# Electronic_load_REVA.net
KiCad netlist of a schematic drawn in Altium Designer
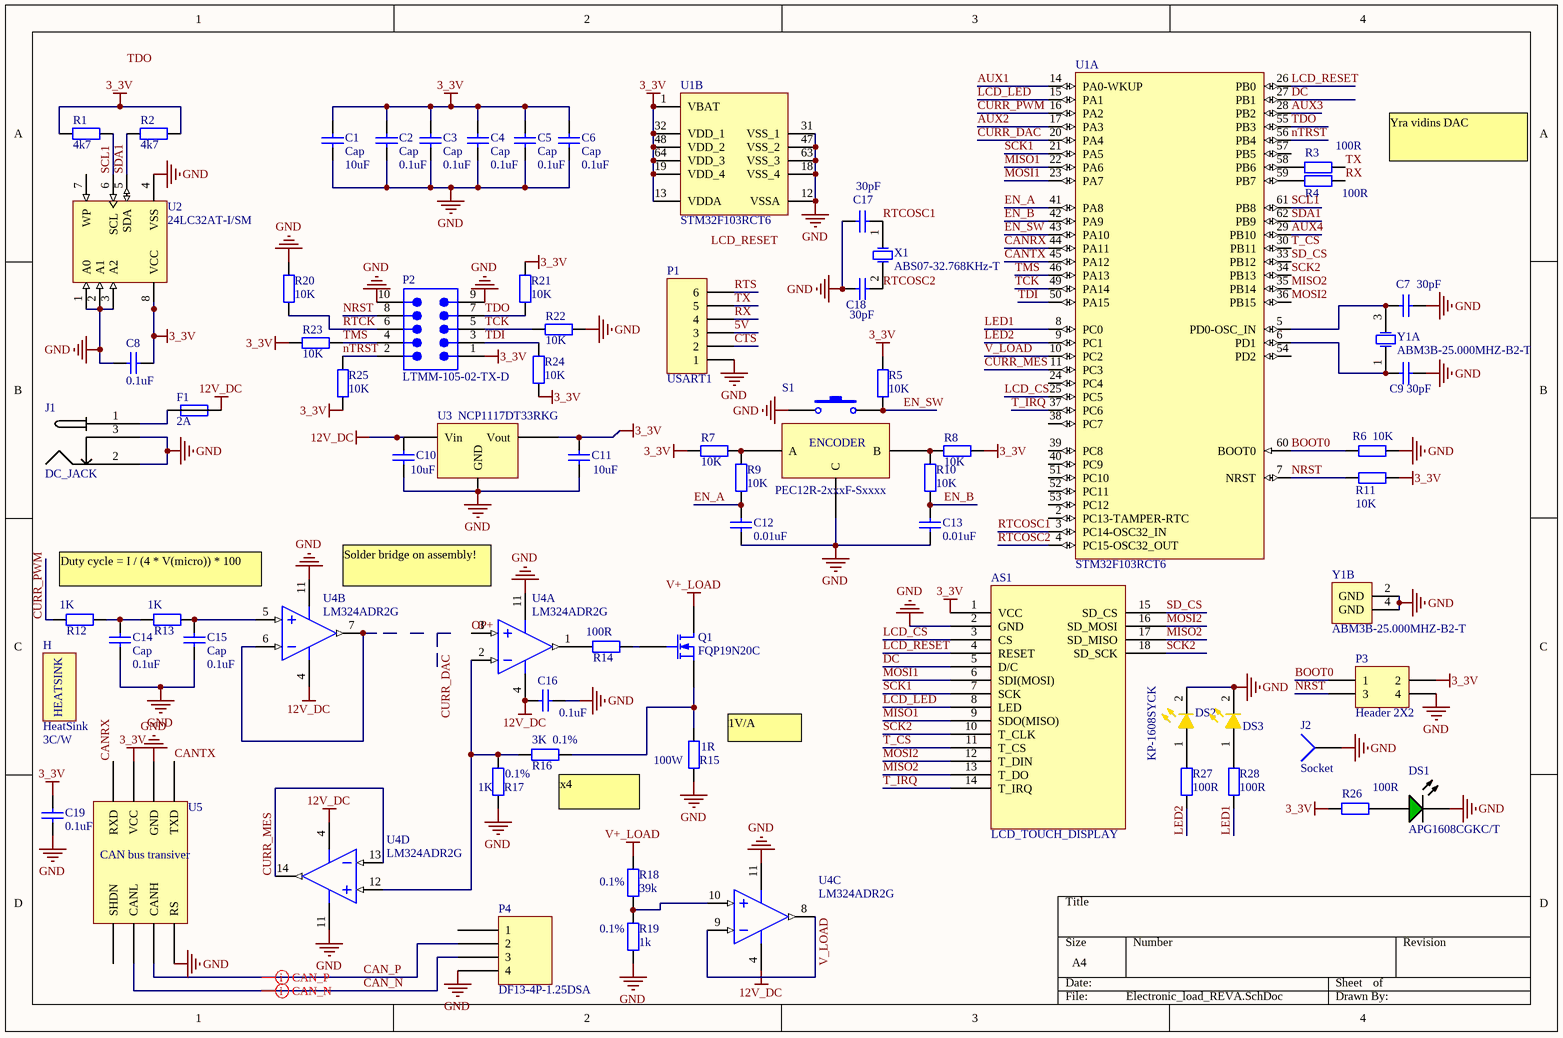
[diagram p0: Electronic_load_REVA.SchDoc]

(export (version "E")
  (design (tool "Eeschema 10.0.6"))
  (components
    (comp (ref "AS1")
      (value "LCD_TOUCH_DISPLAY")
      (footprint "LCD_SPI")
      (libsource (lib "Schlib1") (part "LCD_SPI"))
    )
    (comp (ref "C1")
      (value "Cap")
      (footprint "1206_CAP")
      (description "Capacitor")
      (fields (field (name "ALTIUM_VALUE") "10uF") (field (name "PUBLISHER") "Altium Limited"))
      (libsource (lib "Schlib1") (part "Cap"))
    )
    (comp (ref "C2")
      (value "Cap")
      (footprint "0603_CAP")
      (description "Capacitor")
      (fields (field (name "ALTIUM_VALUE") "0.1uF") (field (name "PUBLISHER") "Altium Limited"))
      (libsource (lib "Schlib1") (part "Cap"))
    )
    (comp (ref "C3")
      (value "Cap")
      (footprint "0603_CAP")
      (description "Capacitor")
      (fields (field (name "ALTIUM_VALUE") "0.1uF") (field (name "PUBLISHER") "Altium Limited"))
      (libsource (lib "Schlib1") (part "Cap"))
    )
    (comp (ref "C4")
      (value "Cap")
      (footprint "0603_CAP")
      (description "Capacitor")
      (fields (field (name "ALTIUM_VALUE") "0.1uF") (field (name "PUBLISHER") "Altium Limited"))
      (libsource (lib "Schlib1") (part "Cap"))
    )
    (comp (ref "C5")
      (value "Cap")
      (footprint "0603_CAP")
      (description "Capacitor")
      (fields (field (name "ALTIUM_VALUE") "0.1uF") (field (name "PUBLISHER") "Altium Limited"))
      (libsource (lib "Schlib1") (part "Cap"))
    )
    (comp (ref "C6")
      (value "Cap")
      (footprint "0603_CAP")
      (description "Capacitor")
      (fields (field (name "ALTIUM_VALUE") "0.1uF") (field (name "PUBLISHER") "Altium Limited"))
      (libsource (lib "Schlib1") (part "Cap"))
    )
    (comp (ref "C7")
      (value "30pF")
      (footprint "0603_CAP")
      (description "Capacitor")
      (fields (field (name "Comment") "Cap") (field (name "PUBLISHER") "Altium Limited"))
      (libsource (lib "Schlib1") (part "Cap"))
    )
    (comp (ref "C8")
      (value "0.1uF")
      (footprint "0603_CAP")
      (description "Capacitor")
      (fields (field (name "Comment") "Cap") (field (name "PUBLISHER") "Altium Limited"))
      (libsource (lib "Schlib1") (part "Cap"))
    )
    (comp (ref "C9")
      (value "30pF")
      (footprint "0603_CAP")
      (description "Capacitor")
      (fields (field (name "Comment") "Cap") (field (name "PUBLISHER") "Altium Limited"))
      (libsource (lib "Schlib1") (part "Cap"))
    )
    (comp (ref "C10")
      (value "10uF")
      (footprint "1206_CAP")
      (description "Capacitor")
      (fields (field (name "Comment") "Cap") (field (name "PUBLISHER") "Altium Limited"))
      (libsource (lib "Schlib1") (part "Cap"))
    )
    (comp (ref "C11")
      (value "10uF")
      (footprint "1206_CAP")
      (description "Capacitor")
      (fields (field (name "Comment") "Cap") (field (name "PUBLISHER") "Altium Limited"))
      (libsource (lib "Schlib1") (part "Cap"))
    )
    (comp (ref "C12")
      (value "0.01uF")
      (footprint "0603_CAP")
      (description "Capacitor")
      (fields (field (name "Comment") "ap") (field (name "PUBLISHER") "Altium Limited"))
      (libsource (lib "Schlib1") (part "Cap"))
    )
    (comp (ref "C13")
      (value "0.01uF")
      (footprint "0603_CAP")
      (description "Capacitor")
      (fields (field (name "Comment") "ap") (field (name "PUBLISHER") "Altium Limited"))
      (libsource (lib "Schlib1") (part "Cap"))
    )
    (comp (ref "C14")
      (value "Cap")
      (footprint "0603_CAP")
      (description "Capacitor")
      (fields (field (name "ALTIUM_VALUE") "0.1uF") (field (name "PUBLISHER") "Altium Limited"))
      (libsource (lib "Schlib1") (part "Cap"))
    )
    (comp (ref "C15")
      (value "Cap")
      (footprint "0603_CAP")
      (description "Capacitor")
      (fields (field (name "ALTIUM_VALUE") "0.1uF") (field (name "PUBLISHER") "Altium Limited"))
      (libsource (lib "Schlib1") (part "Cap"))
    )
    (comp (ref "C16")
      (value "0.1uF")
      (footprint "0603_CAP")
      (description "Capacitor")
      (fields (field (name "Comment") "Cap") (field (name "PUBLISHER") "Altium Limited"))
      (libsource (lib "Schlib1") (part "Cap"))
    )
    (comp (ref "C17")
      (value "30pF")
      (footprint "0603_CAP")
      (description "Capacitor")
      (fields (field (name "Comment") "Cap") (field (name "PUBLISHER") "Altium Limited"))
      (libsource (lib "Schlib1") (part "Cap"))
    )
    (comp (ref "C18")
      (value "30pF")
      (footprint "0603_CAP")
      (description "Capacitor")
      (fields (field (name "Comment") "Cap") (field (name "PUBLISHER") "Altium Limited"))
      (libsource (lib "Schlib1") (part "Cap"))
    )
    (comp (ref "C19")
      (value "0.1uF")
      (footprint "0603_CAP")
      (fields (field (name "Comment") "Cap"))
      (libsource (lib "UAV lib") (part "Cap"))
    )
    (comp (ref "DS1")
      (value "APG1608CGKC/T")
      (footprint "KING-LED0603-25-GREEN_V")
      (description "LED, SMT, 0603(1608), 0.25mm Thickness, Green")
      (libsource (lib "Altium Content Vault") (part "KING-LED_GREEN_A1K2-2"))
    )
    (comp (ref "DS2")
      (value "KP-1608SYCK")
      (footprint "KING-0603LED_YELLOW_V")
      (description "LED, SMT, 0603(1608), 1.1mm thickness, Yellow")
      (fields (field (name "MANUFACTURER") "Kingbright"))
      (libsource (lib "Altium Content Vault") (part "KING-LED-YELLOW-A1K2-2"))
    )
    (comp (ref "DS3")
      (value "KP-1608SYCK")
      (footprint "KING-0603LED_YELLOW_V")
      (description "LED, SMT, 0603(1608), 1.1mm thickness, Yellow")
      (fields (field (name "MANUFACTURER") "Kingbright"))
      (libsource (lib "Altium Content Vault") (part "CMP-0404-00003-1"))
    )
    (comp (ref "F1")
      (value "Fuse")
      (footprint "0603_RES")
      (fields (field (name "CURRENT") "2A"))
      (libsource (lib "Schlib1") (part "Fuse"))
    )
    (comp (ref "H")
      (value "HeatSink")
      (footprint "Heat_Sink")
      (fields (field (name "ALTIUM_UNNAMED_1") "3C/W"))
      (libsource (lib "Schlib1") (part "HeatSink"))
    )
    (comp (ref "J1")
      (value "DC_JACK")
      (footprint "DC_JACK_6.3mm")
      (libsource (lib "Schlib1") (part "DC_JACK"))
    )
    (comp (ref "J2")
      (value "Socket")
      (footprint "PIN1")
      (fields (field (name "PUBLISHER") "Altium Limited"))
      (libsource (lib "Miscellaneous Connectors") (part "Socket"))
    )
    (comp (ref "P1")
      (value "USART1")
      (footprint "HDR1X6")
      (description "Header, 6-Pin")
      (fields (field (name "PUBLISHER") "Altium Limited"))
      (libsource (lib "Miscellaneous Connectors") (part "Header 6"))
    )
    (comp (ref "P2")
      (value "LTMM-105-02-TX-D")
      (footprint "SMTC-LTMM-105-02-XX-D")
      (description "Shrouded Header & Stacker, Through-Hole, Vertical, -55 to 105 degC, 2 mm Pitch, 10-Pin, Male, RoHS")
      (fields (field (name "MANUFACTURER") "Samtec"))
      (libsource (lib "Altium Content Vault") (part "SMTC-LTMM-105-02-X-D"))
    )
    (comp (ref "P3")
      (value "Header 2X2")
      (footprint "HDR2X2")
      (description "Header, 2-Pin, Dual row")
      (fields (field (name "PUBLISHER") "Altium Limited"))
      (libsource (lib "Miscellaneous Connectors") (part "Header 2X2"))
    )
    (comp (ref "P4")
      (value "DF13-4P-1.25DSA")
      (footprint "DF13-4P-1.25DSA")
      (libsource (lib "UAV lib") (part "DF13-4P-1.25DSA"))
    )
    (comp (ref "Q1")
      (value "FQP19N20C")
      (footprint "TO220V")
      (description "N-channel MOSFET")
      (libsource (lib "Schlib1") (part "MOSSFET N-Channel"))
    )
    (comp (ref "R1")
      (value "4k7")
      (footprint "0603_RES")
      (fields (field (name "POWER") "0.125W") (field (name "TOLERANCE") "1%") (field (name "Comment") "Res"))
      (libsource (lib "") (part "Res_1"))
    )
    (comp (ref "R2")
      (value "4k7")
      (footprint "0603_RES")
      (fields (field (name "POWER") "0.125W") (field (name "TOLERANCE") "1%") (field (name "Comment") "Res"))
      (libsource (lib "") (part "Res_1"))
    )
    (comp (ref "R3")
      (value "100R")
      (footprint "0603_RES")
      (fields (field (name "POWER") "0.125W") (field (name "TOLERANCE") "1%") (field (name "Comment") "Res"))
      (libsource (lib "Schlib1") (part "Res"))
    )
    (comp (ref "R4")
      (value "100R")
      (footprint "0603_RES")
      (fields (field (name "POWER") "0.125W") (field (name "TOLERANCE") "1%") (field (name "Comment") "Res"))
      (libsource (lib "Schlib1") (part "Res"))
    )
    (comp (ref "R5")
      (value "10K")
      (footprint "0603_RES")
      (fields (field (name "POWER") "0.125W") (field (name "TOLERANCE") "1%") (field (name "Comment") "Res"))
      (libsource (lib "") (part "Res_3"))
    )
    (comp (ref "R6")
      (value "10K")
      (footprint "0603_RES")
      (fields (field (name "POWER") "0.125W") (field (name "TOLERANCE") "1%") (field (name "Comment") "Res"))
      (libsource (lib "") (part "Res_1"))
    )
    (comp (ref "R7")
      (value "10K")
      (footprint "0603_RES")
      (fields (field (name "POWER") "0.125W") (field (name "TOLERANCE") "1%") (field (name "Comment") "Res"))
      (libsource (lib "Schlib1") (part "Res"))
    )
    (comp (ref "R8")
      (value "10K")
      (footprint "0603_RES")
      (fields (field (name "POWER") "0.125W") (field (name "TOLERANCE") "1%") (field (name "Comment") "Res"))
      (libsource (lib "Schlib1") (part "Res"))
    )
    (comp (ref "R9")
      (value "10K")
      (footprint "0603_RES")
      (fields (field (name "POWER") "0.125W") (field (name "TOLERANCE") "1%") (field (name "Comment") "Res"))
      (libsource (lib "") (part "Res_2"))
    )
    (comp (ref "R10")
      (value "10K")
      (footprint "0603_RES")
      (fields (field (name "POWER") "0.125W") (field (name "TOLERANCE") "1%") (field (name "Comment") "Res"))
      (libsource (lib "") (part "Res_2"))
    )
    (comp (ref "R11")
      (value "10K")
      (footprint "0603_RES")
      (fields (field (name "POWER") "0.125W") (field (name "TOLERANCE") "1%") (field (name "Comment") "Res"))
      (libsource (lib "") (part "Res_1"))
    )
    (comp (ref "R12")
      (value "1K")
      (footprint "0603_RES")
      (fields (field (name "POWER") "0.125W") (field (name "TOLERANCE") "1%") (field (name "Comment") "Res"))
      (libsource (lib "") (part "Res_1"))
    )
    (comp (ref "R13")
      (value "1K")
      (footprint "0603_RES")
      (fields (field (name "POWER") "0.125W") (field (name "TOLERANCE") "1%") (field (name "Comment") "Res"))
      (libsource (lib "") (part "Res_1"))
    )
    (comp (ref "R14")
      (value "100R")
      (footprint "0603_RES")
      (fields (field (name "POWER") "0.125W") (field (name "TOLERANCE") "1%") (field (name "Comment") "Res"))
      (libsource (lib "") (part "Res_1"))
    )
    (comp (ref "R15")
      (value "1R")
      (footprint "100W_res")
      (fields
        (field (name "POWER") "100W")
        (field (name "TOLERANCE") "5%")
        (field (name "PART_NUMBER") "Ebay")
        (field (name "Comment") "Res")
      )
      (libsource (lib "") (part "Res_3"))
    )
    (comp (ref "R16")
      (value "3K")
      (footprint "0603_RES")
      (fields
        (field (name "POWER") "0.125W")
        (field (name "TOLERANCE") "0.1%")
        (field (name "Comment") "Res")
      )
      (libsource (lib "Schlib1") (part "Res"))
    )
    (comp (ref "R17")
      (value "1K")
      (footprint "0603_RES")
      (fields
        (field (name "POWER") "0.125W")
        (field (name "TOLERANCE") "0.1%")
        (field (name "Comment") "Res")
      )
      (libsource (lib "") (part "Res_3"))
    )
    (comp (ref "R18")
      (value "39k")
      (footprint "0603_RES")
      (fields
        (field (name "POWER") "0.125W")
        (field (name "TOLERANCE") "0.1%")
        (field (name "Comment") "Res")
      )
      (libsource (lib "") (part "Res_2"))
    )
    (comp (ref "R19")
      (value "1k")
      (footprint "0603_RES")
      (fields
        (field (name "POWER") "0.125W")
        (field (name "TOLERANCE") "0.1%")
        (field (name "Comment") "Res")
      )
      (libsource (lib "") (part "Res_2"))
    )
    (comp (ref "R20")
      (value "10K")
      (footprint "0603_RES")
      (fields (field (name "POWER") "0.125W") (field (name "TOLERANCE") "1%") (field (name "Comment") "Res"))
      (libsource (lib "") (part "Res_2"))
    )
    (comp (ref "R21")
      (value "10K")
      (footprint "0603_RES")
      (fields (field (name "POWER") "0.125W") (field (name "TOLERANCE") "1%") (field (name "Comment") "Res"))
      (libsource (lib "") (part "Res_3"))
    )
    (comp (ref "R22")
      (value "10K")
      (footprint "0603_RES")
      (fields (field (name "POWER") "0.125W") (field (name "TOLERANCE") "1%") (field (name "Comment") "Res"))
      (libsource (lib "Schlib1") (part "Res"))
    )
    (comp (ref "R23")
      (value "10K")
      (footprint "0603_RES")
      (fields (field (name "POWER") "0.125W") (field (name "TOLERANCE") "1%") (field (name "Comment") "Res"))
      (libsource (lib "") (part "Res_1"))
    )
    (comp (ref "R24")
      (value "10K")
      (footprint "0603_RES")
      (fields (field (name "POWER") "0.125W") (field (name "TOLERANCE") "1%") (field (name "Comment") "Res"))
      (libsource (lib "") (part "Res_3"))
    )
    (comp (ref "R25")
      (value "10K")
      (footprint "0603_RES")
      (fields (field (name "POWER") "0.125W") (field (name "TOLERANCE") "1%") (field (name "Comment") "Res"))
      (libsource (lib "") (part "Res_3"))
    )
    (comp (ref "R26")
      (value "100R")
      (footprint "0603_RES")
      (fields (field (name "POWER") "0.125W") (field (name "TOLERANCE") "1%") (field (name "Comment") "Res"))
      (libsource (lib "Schlib1") (part "Res"))
    )
    (comp (ref "R27")
      (value "100R")
      (footprint "0603_RES")
      (fields (field (name "POWER") "0.125W") (field (name "TOLERANCE") "1%") (field (name "Comment") "Res"))
      (libsource (lib "") (part "Res_2"))
    )
    (comp (ref "R28")
      (value "100R")
      (footprint "0603_RES")
      (fields (field (name "POWER") "0.125W") (field (name "TOLERANCE") "1%") (field (name "Comment") "Res"))
      (libsource (lib "") (part "Res_2"))
    )
    (comp (ref "S1")
      (value "PEC12R-2xxxF-Sxxxx")
      (footprint "Rotary_encoder_ver")
      (libsource (lib "Schlib1") (part "PEC12R-2xxxF-Sxxxx"))
    )
    (comp (ref "U1")
      (value "STM32F103RCT6")
      (footprint "LQFP64_N")
      (libsource (lib "Altium Content Vault") (part "MC-ARM-STM32F101-SQ64"))
    )
    (comp (ref "U2")
      (value "24LC32AT-I/SM")
      (footprint "SOIJ-SM8_L")
      (description "32Kbit, 400kHz, 2.5V, I2C Serial EEPROM, 8-Pin SOIC 208mil, Industrial Temperature, Tape and Reel")
      (libsource (lib "Altium Content Vault") (part "MEM-SEEPROM-34AA02-IL8"))
    )
    (comp (ref "U3")
      (value "NCP1117DT33RKG")
      (footprint "TO-252")
      (libsource (lib "Schlib1") (part "Linear"))
    )
    (comp (ref "U4")
      (value "LM324ADR2G")
      (footprint "ONSC-SOIC-14-751A-03_V")
      (fields (field (name "MANUFACTURER") "On Semiconductor"))
      (libsource (lib "Altium Content Vault") (part "ONSC-LM224_324_2902_NCV2902-14"))
    )
    (comp (ref "U5")
      (value "CAN bus transiver")
      (footprint "SOIC127P600X175-8M")
      (libsource (lib "UAV lib") (part "MAX3051"))
    )
    (comp (ref "X1")
      (value "ABS07-32.768KHz-T")
      (footprint "ABRA-ABS07-2_V")
      (description "Crystal, 32.768 kHz, 12.5 pF, -40 to 85 degC, SMD Low Profile 3.2 x 1.5 x 0.9 mm, Tape and Reel")
      (fields (field (name "MANUFACTURER") "Abracon"))
      (libsource (lib "Altium Content Vault") (part "ABRA-ABS07-2"))
    )
    (comp (ref "Y1")
      (value "ABM3B-25.000MHZ-B2-T")
      (footprint "ABRA-ABM3B-4_V")
      (description "Crystal, SMD, 25.000000MHz Stab=50ppm 18.0pF")
      (fields (field (name "MANUFACTURER") "Abracon"))
      (libsource (lib "") (part "ABRA-ABM3B-4_1"))
    )
  )
  (nets
    (net (code "1") (name "/5V") (class "Default")
      (node (ref "P1") (pin "3") (pinfunction "3_3") (pintype "passive"))
    )
    (net (code "2") (name "/AUX1") (class "Default")
      (node (ref "U1") (pin "14") (pinfunction "PA0-WKUP_14") (pintype "bidirectional"))
    )
    (net (code "3") (name "/AUX2") (class "Default")
      (node (ref "U1") (pin "17") (pinfunction "PA3_17") (pintype "bidirectional"))
    )
    (net (code "4") (name "/AUX3") (class "Default")
      (node (ref "U1") (pin "28") (pinfunction "PB2_28") (pintype "bidirectional"))
    )
    (net (code "5") (name "/AUX4") (class "Default")
      (node (ref "U1") (pin "29") (pinfunction "PB10_29") (pintype "bidirectional"))
    )
    (net (code "6") (name "/BOOT0") (class "Default")
      (node (ref "P3") (pin "1") (pinfunction "1_1") (pintype "passive"))
      (node (ref "R6") (pin "1") (pinfunction "1_1") (pintype "passive"))
      (node (ref "U1") (pin "60") (pinfunction "BOOT0_60") (pintype "input"))
    )
    (net (code "7") (name "/CANRX") (class "Default")
      (node (ref "U1") (pin "44") (pinfunction "PA11_44") (pintype "bidirectional"))
      (node (ref "U5") (pin "4") (pinfunction "RXD_4") (pintype "passive"))
    )
    (net (code "8") (name "/CANTX") (class "Default")
      (node (ref "U1") (pin "45") (pinfunction "PA12_45") (pintype "bidirectional"))
      (node (ref "U5") (pin "1") (pinfunction "TXD_1") (pintype "passive"))
    )
    (net (code "9") (name "/CAN_N") (class "Default")
      (node (ref "P4") (pin "3") (pinfunction "3_3") (pintype "passive"))
      (node (ref "U5") (pin "6") (pinfunction "CANL_6") (pintype "passive"))
    )
    (net (code "10") (name "/CAN_P") (class "Default")
      (node (ref "P4") (pin "2") (pinfunction "2_2") (pintype "passive"))
      (node (ref "U5") (pin "7") (pinfunction "CANH_7") (pintype "passive"))
    )
    (net (code "11") (name "/CTS") (class "Default")
      (node (ref "P1") (pin "2") (pinfunction "2_2") (pintype "passive"))
    )
    (net (code "12") (name "/CURR_DAC") (class "Default")
      (node (ref "U1") (pin "20") (pinfunction "PA4_20") (pintype "bidirectional"))
    )
    (net (code "13") (name "/CURR_MES") (class "Default")
      (node (ref "U1") (pin "11") (pinfunction "PC3_11") (pintype "bidirectional"))
      (node (ref "U4") (pin "13") (pinfunction "IN4-_13") (pintype "input"))
      (node (ref "U4") (pin "14") (pinfunction "OUT4_14") (pintype "output"))
    )
    (net (code "14") (name "/CURR_PWM") (class "Default")
      (node (ref "R12") (pin "1") (pinfunction "1_1") (pintype "passive"))
      (node (ref "U1") (pin "16") (pinfunction "PA2_16") (pintype "bidirectional"))
    )
    (net (code "15") (name "/DC") (class "Default")
      (node (ref "AS1") (pin "5") (pinfunction "D/C_5") (pintype "passive"))
      (node (ref "U1") (pin "27") (pinfunction "PB1_27") (pintype "bidirectional"))
    )
    (net (code "16") (name "/EN_A") (class "Default")
      (node (ref "C12") (pin "2") (pinfunction "2_2") (pintype "passive"))
      (node (ref "R9") (pin "2") (pinfunction "2_2") (pintype "passive"))
      (node (ref "U1") (pin "41") (pinfunction "PA8_41") (pintype "bidirectional"))
    )
    (net (code "17") (name "/EN_B") (class "Default")
      (node (ref "C13") (pin "2") (pinfunction "2_2") (pintype "passive"))
      (node (ref "R10") (pin "2") (pinfunction "2_2") (pintype "passive"))
      (node (ref "U1") (pin "42") (pinfunction "PA9_42") (pintype "bidirectional"))
    )
    (net (code "18") (name "/EN_SW") (class "Default")
      (node (ref "R5") (pin "1") (pinfunction "1_1") (pintype "passive"))
      (node (ref "S1") (pin "2") (pinfunction "2_2") (pintype "passive"))
      (node (ref "U1") (pin "43") (pinfunction "PA10_43") (pintype "bidirectional"))
    )
    (net (code "19") (name "/LCD_CS") (class "Default")
      (node (ref "AS1") (pin "3") (pinfunction "CS_3") (pintype "passive"))
      (node (ref "U1") (pin "25") (pinfunction "PC5_25") (pintype "bidirectional"))
    )
    (net (code "20") (name "/LCD_LED") (class "Default")
      (node (ref "AS1") (pin "8") (pinfunction "LED_8") (pintype "passive"))
      (node (ref "U1") (pin "15") (pinfunction "PA1_15") (pintype "bidirectional"))
    )
    (net (code "21") (name "/LCD_RESET") (class "Default")
      (node (ref "AS1") (pin "4") (pinfunction "RESET_4") (pintype "passive"))
      (node (ref "U1") (pin "26") (pinfunction "PB0_26") (pintype "bidirectional"))
    )
    (net (code "22") (name "/LED1") (class "Default")
      (node (ref "R28") (pin "2") (pinfunction "2_2") (pintype "passive"))
      (node (ref "U1") (pin "8") (pinfunction "PC0_8") (pintype "bidirectional"))
    )
    (net (code "23") (name "/LED2") (class "Default")
      (node (ref "R27") (pin "2") (pinfunction "2_2") (pintype "passive"))
      (node (ref "U1") (pin "9") (pinfunction "PC1_9") (pintype "bidirectional"))
    )
    (net (code "24") (name "/MISO1") (class "Default")
      (node (ref "AS1") (pin "9") (pinfunction "SDO(MISO)_9") (pintype "passive"))
      (node (ref "U1") (pin "22") (pinfunction "PA6_22") (pintype "bidirectional"))
    )
    (net (code "25") (name "/MISO2") (class "Default")
      (node (ref "AS1") (pin "13") (pinfunction "T_DO_13") (pintype "passive"))
      (node (ref "AS1") (pin "17") (pinfunction "SD_MISO_17") (pintype "passive"))
      (node (ref "U1") (pin "35") (pinfunction "PB14_35") (pintype "bidirectional"))
    )
    (net (code "26") (name "/MOSI1") (class "Default")
      (node (ref "AS1") (pin "6") (pinfunction "SDI(MOSI)_6") (pintype "passive"))
      (node (ref "U1") (pin "23") (pinfunction "PA7_23") (pintype "bidirectional"))
    )
    (net (code "27") (name "/MOSI2") (class "Default")
      (node (ref "AS1") (pin "12") (pinfunction "T_DIN_12") (pintype "passive"))
      (node (ref "AS1") (pin "16") (pinfunction "SD_MOSI_16") (pintype "passive"))
      (node (ref "U1") (pin "36") (pinfunction "PB15_36") (pintype "bidirectional"))
    )
    (net (code "28") (name "/NRST") (class "Default")
      (node (ref "P2") (pin "8") (pinfunction "8_8") (pintype "passive"))
      (node (ref "P3") (pin "3") (pinfunction "3_3") (pintype "passive"))
      (node (ref "R11") (pin "1") (pinfunction "1_1") (pintype "passive"))
      (node (ref "U1") (pin "7") (pinfunction "NRST_7") (pintype "bidirectional"))
    )
    (net (code "29") (name "/OP+") (class "Default")
      (node (ref "U4") (pin "3") (pinfunction "IN1+_3") (pintype "input"))
    )
    (net (code "30") (name "/RTCK") (class "Default")
      (node (ref "P2") (pin "6") (pinfunction "6_6") (pintype "passive"))
      (node (ref "R20") (pin "2") (pinfunction "2_2") (pintype "passive"))
    )
    (net (code "31") (name "/RTCOSC1") (class "Default")
      (node (ref "C17") (pin "2") (pinfunction "2_2") (pintype "passive"))
      (node (ref "U1") (pin "3") (pinfunction "PC14-OSC32_IN_3") (pintype "bidirectional"))
      (node (ref "X1") (pin "1") (pinfunction "X1_1") (pintype "passive"))
    )
    (net (code "32") (name "/RTCOSC2") (class "Default")
      (node (ref "C18") (pin "2") (pinfunction "2_2") (pintype "passive"))
      (node (ref "U1") (pin "4") (pinfunction "PC15-OSC32_OUT_4") (pintype "bidirectional"))
      (node (ref "X1") (pin "2") (pinfunction "X2_2") (pintype "passive"))
    )
    (net (code "33") (name "/RTS") (class "Default")
      (node (ref "P1") (pin "6") (pinfunction "6_6") (pintype "passive"))
    )
    (net (code "34") (name "/RX") (class "Default")
      (node (ref "P1") (pin "4") (pinfunction "4_4") (pintype "passive"))
      (node (ref "R4") (pin "1") (pinfunction "1_1") (pintype "passive"))
    )
    (net (code "35") (name "/SCK1") (class "Default")
      (node (ref "AS1") (pin "7") (pinfunction "SCK_7") (pintype "passive"))
      (node (ref "U1") (pin "21") (pinfunction "PA5_21") (pintype "bidirectional"))
    )
    (net (code "36") (name "/SCK2") (class "Default")
      (node (ref "AS1") (pin "10") (pinfunction "T_CLK_10") (pintype "passive"))
      (node (ref "AS1") (pin "18") (pinfunction "SD_SCK_18") (pintype "passive"))
      (node (ref "U1") (pin "34") (pinfunction "PB13_34") (pintype "bidirectional"))
    )
    (net (code "37") (name "/SCL1") (class "Default")
      (node (ref "R1") (pin "2") (pinfunction "2_2") (pintype "passive"))
      (node (ref "U1") (pin "61") (pinfunction "PB8_61") (pintype "bidirectional"))
      (node (ref "U2") (pin "6") (pinfunction "SCL_6") (pintype "input"))
    )
    (net (code "38") (name "/SDA1") (class "Default")
      (node (ref "R2") (pin "1") (pinfunction "1_1") (pintype "passive"))
      (node (ref "U1") (pin "62") (pinfunction "PB9_62") (pintype "bidirectional"))
      (node (ref "U2") (pin "5") (pinfunction "SDA_5") (pintype "bidirectional"))
    )
    (net (code "39") (name "/SD_CS") (class "Default")
      (node (ref "AS1") (pin "15") (pinfunction "SD_CS_15") (pintype "passive"))
      (node (ref "U1") (pin "33") (pinfunction "PB12_33") (pintype "bidirectional"))
    )
    (net (code "40") (name "/TCK") (class "Default")
      (node (ref "P2") (pin "5") (pinfunction "5_5") (pintype "passive"))
      (node (ref "R22") (pin "2") (pinfunction "2_2") (pintype "passive"))
      (node (ref "U1") (pin "49") (pinfunction "PA14_49") (pintype "bidirectional"))
    )
    (net (code "41") (name "/TDI") (class "Default")
      (node (ref "P2") (pin "3") (pinfunction "3_3") (pintype "passive"))
      (node (ref "R24") (pin "2") (pinfunction "2_2") (pintype "passive"))
      (node (ref "U1") (pin "50") (pinfunction "PA15_50") (pintype "bidirectional"))
    )
    (net (code "42") (name "/TDO") (class "Default")
      (node (ref "P2") (pin "7") (pinfunction "7_7") (pintype "passive"))
      (node (ref "R21") (pin "1") (pinfunction "1_1") (pintype "passive"))
      (node (ref "U1") (pin "55") (pinfunction "PB3_55") (pintype "bidirectional"))
    )
    (net (code "43") (name "/TMS") (class "Default")
      (node (ref "P2") (pin "4") (pinfunction "4_4") (pintype "passive"))
      (node (ref "R23") (pin "2") (pinfunction "2_2") (pintype "passive"))
      (node (ref "U1") (pin "46") (pinfunction "PA13_46") (pintype "bidirectional"))
    )
    (net (code "44") (name "/TX") (class "Default")
      (node (ref "P1") (pin "5") (pinfunction "5_5") (pintype "passive"))
      (node (ref "R3") (pin "1") (pinfunction "1_1") (pintype "passive"))
    )
    (net (code "45") (name "/T_CS") (class "Default")
      (node (ref "AS1") (pin "11") (pinfunction "T_CS_11") (pintype "passive"))
      (node (ref "U1") (pin "30") (pinfunction "PB11_30") (pintype "bidirectional"))
    )
    (net (code "46") (name "/T_IRQ") (class "Default")
      (node (ref "AS1") (pin "14") (pinfunction "T_IRQ_14") (pintype "passive"))
      (node (ref "U1") (pin "37") (pinfunction "PC6_37") (pintype "bidirectional"))
    )
    (net (code "47") (name "/V_LOAD") (class "Default")
      (node (ref "U1") (pin "10") (pinfunction "PC2_10") (pintype "bidirectional"))
      (node (ref "U4") (pin "8") (pinfunction "OUT3_8") (pintype "output"))
      (node (ref "U4") (pin "9") (pinfunction "IN3-_9") (pintype "input"))
    )
    (net (code "48") (name "/nTRST") (class "Default")
      (node (ref "P2") (pin "2") (pinfunction "2_2") (pintype "passive"))
      (node (ref "R25") (pin "2") (pinfunction "2_2") (pintype "passive"))
      (node (ref "U1") (pin "56") (pinfunction "PB4_56") (pintype "bidirectional"))
    )
    (net (code "49") (name "3_3V") (class "Default")
      (node (ref "AS1") (pin "1") (pinfunction "VCC_1") (pintype "passive"))
      (node (ref "C1") (pin "1") (pinfunction "1_1") (pintype "passive"))
      (node (ref "C11") (pin "1") (pinfunction "1_1") (pintype "passive"))
      (node (ref "C19") (pin "2") (pinfunction "2_2") (pintype "passive"))
      (node (ref "C2") (pin "1") (pinfunction "1_1") (pintype "passive"))
      (node (ref "C3") (pin "1") (pinfunction "1_1") (pintype "passive"))
      (node (ref "C4") (pin "1") (pinfunction "1_1") (pintype "passive"))
      (node (ref "C5") (pin "1") (pinfunction "1_1") (pintype "passive"))
      (node (ref "C6") (pin "1") (pinfunction "1_1") (pintype "passive"))
      (node (ref "C8") (pin "2") (pinfunction "2_2") (pintype "passive"))
      (node (ref "P2") (pin "1") (pinfunction "1_1") (pintype "passive"))
      (node (ref "P3") (pin "2") (pinfunction "2_2") (pintype "passive"))
      (node (ref "R1") (pin "1") (pinfunction "1_1") (pintype "passive"))
      (node (ref "R11") (pin "2") (pinfunction "2_2") (pintype "passive"))
      (node (ref "R2") (pin "2") (pinfunction "2_2") (pintype "passive"))
      (node (ref "R21") (pin "2") (pinfunction "2_2") (pintype "passive"))
      (node (ref "R23") (pin "1") (pinfunction "1_1") (pintype "passive"))
      (node (ref "R24") (pin "1") (pinfunction "1_1") (pintype "passive"))
      (node (ref "R25") (pin "1") (pinfunction "1_1") (pintype "passive"))
      (node (ref "R26") (pin "2") (pinfunction "2_2") (pintype "passive"))
      (node (ref "R5") (pin "2") (pinfunction "2_2") (pintype "passive"))
      (node (ref "R7") (pin "2") (pinfunction "2_2") (pintype "passive"))
      (node (ref "R8") (pin "1") (pinfunction "1_1") (pintype "passive"))
      (node (ref "U1") (pin "1") (pinfunction "VBAT_1") (pintype "power_in"))
      (node (ref "U1") (pin "13") (pinfunction "VDDA_13") (pintype "power_in"))
      (node (ref "U1") (pin "19") (pinfunction "VDD_4_19") (pintype "power_in"))
      (node (ref "U1") (pin "32") (pinfunction "VDD_1_32") (pintype "power_in"))
      (node (ref "U1") (pin "48") (pinfunction "VDD_2_48") (pintype "power_in"))
      (node (ref "U1") (pin "64") (pinfunction "VDD_3_64") (pintype "power_in"))
      (node (ref "U2") (pin "8") (pinfunction "VCC_8") (pintype "power_in"))
      (node (ref "U3") (pin "Vout") (pinfunction "Vout_Vout") (pintype "passive"))
      (node (ref "U5") (pin "3") (pinfunction "VCC_3") (pintype "passive"))
    )
    (net (code "50") (name "12V_DC") (class "Default")
      (node (ref "C10") (pin "1") (pinfunction "1_1") (pintype "passive"))
      (node (ref "C16") (pin "1") (pinfunction "1_1") (pintype "passive"))
      (node (ref "F1") (pin "2") (pinfunction "2_2") (pintype "passive"))
      (node (ref "U3") (pin "Vin") (pinfunction "Vin_Vin") (pintype "passive"))
      (node (ref "U4") (pin "4") (pinfunction "VCC_4") (pintype "power_in"))
    )
    (net (code "51") (name "GND") (class "Default")
      (node (ref "AS1") (pin "2") (pinfunction "GND_2") (pintype "passive"))
      (node (ref "C1") (pin "2") (pinfunction "2_2") (pintype "passive"))
      (node (ref "C10") (pin "2") (pinfunction "2_2") (pintype "passive"))
      (node (ref "C11") (pin "2") (pinfunction "2_2") (pintype "passive"))
      (node (ref "C12") (pin "1") (pinfunction "1_1") (pintype "passive"))
      (node (ref "C13") (pin "1") (pinfunction "1_1") (pintype "passive"))
      (node (ref "C14") (pin "1") (pinfunction "1_1") (pintype "passive"))
      (node (ref "C15") (pin "1") (pinfunction "1_1") (pintype "passive"))
      (node (ref "C16") (pin "2") (pinfunction "2_2") (pintype "passive"))
      (node (ref "C17") (pin "1") (pinfunction "1_1") (pintype "passive"))
      (node (ref "C18") (pin "1") (pinfunction "1_1") (pintype "passive"))
      (node (ref "C19") (pin "1") (pinfunction "1_1") (pintype "passive"))
      (node (ref "C2") (pin "2") (pinfunction "2_2") (pintype "passive"))
      (node (ref "C3") (pin "2") (pinfunction "2_2") (pintype "passive"))
      (node (ref "C4") (pin "2") (pinfunction "2_2") (pintype "passive"))
      (node (ref "C5") (pin "2") (pinfunction "2_2") (pintype "passive"))
      (node (ref "C6") (pin "2") (pinfunction "2_2") (pintype "passive"))
      (node (ref "C7") (pin "2") (pinfunction "2_2") (pintype "passive"))
      (node (ref "C8") (pin "1") (pinfunction "1_1") (pintype "passive"))
      (node (ref "C9") (pin "2") (pinfunction "2_2") (pintype "passive"))
      (node (ref "DS1") (pin "2") (pinfunction "K_2") (pintype "passive"))
      (node (ref "DS2") (pin "2") (pinfunction "K_2") (pintype "passive"))
      (node (ref "DS3") (pin "2") (pinfunction "K_2") (pintype "passive"))
      (node (ref "J1") (pin "2") (pinfunction "2_2") (pintype "passive"))
      (node (ref "J1") (pin "3") (pinfunction "3_3") (pintype "passive"))
      (node (ref "J2") (pin "1") (pinfunction "1_1") (pintype "passive"))
      (node (ref "P1") (pin "1") (pinfunction "1_1") (pintype "passive"))
      (node (ref "P2") (pin "10") (pinfunction "10_10") (pintype "passive"))
      (node (ref "P2") (pin "9") (pinfunction "9_9") (pintype "passive"))
      (node (ref "P3") (pin "4") (pinfunction "4_4") (pintype "passive"))
      (node (ref "P4") (pin "4") (pinfunction "4_4") (pintype "passive"))
      (node (ref "R15") (pin "1") (pinfunction "1_1") (pintype "passive"))
      (node (ref "R17") (pin "1") (pinfunction "1_1") (pintype "passive"))
      (node (ref "R19") (pin "2") (pinfunction "2_2") (pintype "passive"))
      (node (ref "R20") (pin "1") (pinfunction "1_1") (pintype "passive"))
      (node (ref "R22") (pin "1") (pinfunction "1_1") (pintype "passive"))
      (node (ref "R6") (pin "2") (pinfunction "2_2") (pintype "passive"))
      (node (ref "S1") (pin "1") (pinfunction "1_1") (pintype "passive"))
      (node (ref "S1") (pin "C") (pinfunction "C_C") (pintype "passive"))
      (node (ref "U1") (pin "12") (pinfunction "VSSA_12") (pintype "power_in"))
      (node (ref "U1") (pin "18") (pinfunction "VSS_4_18") (pintype "power_in"))
      (node (ref "U1") (pin "31") (pinfunction "VSS_1_31") (pintype "power_in"))
      (node (ref "U1") (pin "47") (pinfunction "VSS_2_47") (pintype "power_in"))
      (node (ref "U1") (pin "63") (pinfunction "VSS_3_63") (pintype "power_in"))
      (node (ref "U2") (pin "1") (pinfunction "A0_1") (pintype "input"))
      (node (ref "U2") (pin "2") (pinfunction "A1_2") (pintype "input"))
      (node (ref "U2") (pin "3") (pinfunction "A2_3") (pintype "input"))
      (node (ref "U2") (pin "4") (pinfunction "VSS_4") (pintype "power_in"))
      (node (ref "U3") (pin "GN") (pinfunction "GND_GN") (pintype "passive"))
      (node (ref "U4") (pin "11") (pinfunction "VEE/GND_11") (pintype "power_in"))
      (node (ref "U5") (pin "2") (pinfunction "GND_2") (pintype "passive"))
      (node (ref "U5") (pin "8") (pinfunction "RS_8") (pintype "passive"))
      (node (ref "Y1") (pin "2") (pinfunction "GND_2") (pintype "power_in"))
      (node (ref "Y1") (pin "4") (pinfunction "GND_4") (pintype "power_in"))
    )
    (net (code "52") (name "Net-(C14-Pad2)") (class "Default")
      (node (ref "C14") (pin "2") (pinfunction "2_2") (pintype "passive"))
      (node (ref "R12") (pin "2") (pinfunction "2_2") (pintype "passive"))
      (node (ref "R13") (pin "1") (pinfunction "1_1") (pintype "passive"))
    )
    (net (code "53") (name "Net-(DS1-A)") (class "Default")
      (node (ref "DS1") (pin "1") (pinfunction "A_1") (pintype "passive"))
      (node (ref "R26") (pin "1") (pinfunction "1_1") (pintype "passive"))
    )
    (net (code "54") (name "Net-(DS2-A)") (class "Default")
      (node (ref "DS2") (pin "1") (pinfunction "A_1") (pintype "passive"))
      (node (ref "R27") (pin "1") (pinfunction "1_1") (pintype "passive"))
    )
    (net (code "55") (name "Net-(DS3-A)") (class "Default")
      (node (ref "DS3") (pin "1") (pinfunction "A_1") (pintype "passive"))
      (node (ref "R28") (pin "1") (pinfunction "1_1") (pintype "passive"))
    )
    (net (code "56") (name "Net-(F1-Pad1)") (class "Default")
      (node (ref "F1") (pin "1") (pinfunction "1_1") (pintype "passive"))
      (node (ref "J1") (pin "1") (pinfunction "1_1") (pintype "passive"))
    )
    (net (code "57") (name "Net-(Q1-PadG)") (class "Default")
      (node (ref "Q1") (pin "G") (pinfunction "G_G") (pintype "passive"))
      (node (ref "R14") (pin "2") (pinfunction "2_2") (pintype "passive"))
    )
    (net (code "58") (name "Net-(Q1-PadS)") (class "Default")
      (node (ref "Q1") (pin "S") (pinfunction "S_S") (pintype "passive"))
      (node (ref "R15") (pin "2") (pinfunction "2_2") (pintype "passive"))
      (node (ref "R16") (pin "1") (pinfunction "1_1") (pintype "passive"))
    )
    (net (code "59") (name "Net-(R7-Pad1)") (class "Default")
      (node (ref "R7") (pin "1") (pinfunction "1_1") (pintype "passive"))
      (node (ref "R9") (pin "1") (pinfunction "1_1") (pintype "passive"))
      (node (ref "S1") (pin "A") (pinfunction "A_A") (pintype "passive"))
    )
    (net (code "60") (name "Net-(R10-Pad1)") (class "Default")
      (node (ref "R10") (pin "1") (pinfunction "1_1") (pintype "passive"))
      (node (ref "R8") (pin "2") (pinfunction "2_2") (pintype "passive"))
      (node (ref "S1") (pin "B") (pinfunction "B_B") (pintype "passive"))
    )
    (net (code "61") (name "Net-(U1A-PB6)") (class "Default")
      (node (ref "R3") (pin "2") (pinfunction "2_2") (pintype "passive"))
      (node (ref "U1") (pin "58") (pinfunction "PB6_58") (pintype "bidirectional"))
    )
    (net (code "62") (name "Net-(U1A-PB7)") (class "Default")
      (node (ref "R4") (pin "2") (pinfunction "2_2") (pintype "passive"))
      (node (ref "U1") (pin "59") (pinfunction "PB7_59") (pintype "bidirectional"))
    )
    (net (code "63") (name "Net-(U1A-PD0-OSC_IN)") (class "Default")
      (node (ref "C7") (pin "1") (pinfunction "1_1") (pintype "passive"))
      (node (ref "U1") (pin "5") (pinfunction "PD0-OSC_IN_5") (pintype "bidirectional"))
      (node (ref "Y1") (pin "3") (pinfunction "X2_3") (pintype "passive"))
    )
    (net (code "64") (name "Net-(U1A-PD1)") (class "Default")
      (node (ref "C9") (pin "1") (pinfunction "1_1") (pintype "passive"))
      (node (ref "U1") (pin "6") (pinfunction "PD1_6") (pintype "bidirectional"))
      (node (ref "Y1") (pin "1") (pinfunction "X1_1") (pintype "passive"))
    )
    (net (code "65") (name "Net-(U4A-IN1-)") (class "Default")
      (node (ref "R16") (pin "2") (pinfunction "2_2") (pintype "passive"))
      (node (ref "R17") (pin "2") (pinfunction "2_2") (pintype "passive"))
      (node (ref "U4") (pin "12") (pinfunction "IN4+_12") (pintype "input"))
      (node (ref "U4") (pin "2") (pinfunction "IN1-_2") (pintype "input"))
    )
    (net (code "66") (name "Net-(U4A-OUT1)") (class "Default")
      (node (ref "R14") (pin "1") (pinfunction "1_1") (pintype "passive"))
      (node (ref "U4") (pin "1") (pinfunction "OUT1_1") (pintype "output"))
    )
    (net (code "67") (name "Net-(U4B-IN2+)") (class "Default")
      (node (ref "C15") (pin "2") (pinfunction "2_2") (pintype "passive"))
      (node (ref "R13") (pin "2") (pinfunction "2_2") (pintype "passive"))
      (node (ref "U4") (pin "5") (pinfunction "IN2+_5") (pintype "input"))
    )
    (net (code "68") (name "Net-(U4B-IN2-)") (class "Default")
      (node (ref "U4") (pin "6") (pinfunction "IN2-_6") (pintype "input"))
      (node (ref "U4") (pin "7") (pinfunction "OUT2_7") (pintype "output"))
    )
    (net (code "69") (name "Net-(U4C-IN3+)") (class "Default")
      (node (ref "R18") (pin "2") (pinfunction "2_2") (pintype "passive"))
      (node (ref "R19") (pin "1") (pinfunction "1_1") (pintype "passive"))
      (node (ref "U4") (pin "10") (pinfunction "IN3+_10") (pintype "input"))
    )
    (net (code "70") (name "V+_LOAD") (class "Default")
      (node (ref "Q1") (pin "D") (pinfunction "D_D") (pintype "passive"))
      (node (ref "R18") (pin "1") (pinfunction "1_1") (pintype "passive"))
    )
    (net (code "71") (name "unconnected-(P4-Pad1)") (class "Default")
      (node (ref "P4") (pin "1") (pinfunction "1_1") (pintype "passive"))
    )
    (net (code "72") (name "unconnected-(U1A-PB5-Pad57)") (class "Default")
      (node (ref "U1") (pin "57") (pinfunction "PB5_57") (pintype "bidirectional"))
    )
    (net (code "73") (name "unconnected-(U1A-PC4-Pad24)") (class "Default")
      (node (ref "U1") (pin "24") (pinfunction "PC4_24") (pintype "bidirectional"))
    )
    (net (code "74") (name "unconnected-(U1A-PC7-Pad38)") (class "Default")
      (node (ref "U1") (pin "38") (pinfunction "PC7_38") (pintype "bidirectional"))
    )
    (net (code "75") (name "unconnected-(U1A-PC8-Pad39)") (class "Default")
      (node (ref "U1") (pin "39") (pinfunction "PC8_39") (pintype "bidirectional"))
    )
    (net (code "76") (name "unconnected-(U1A-PC9-Pad40)") (class "Default")
      (node (ref "U1") (pin "40") (pinfunction "PC9_40") (pintype "bidirectional"))
    )
    (net (code "77") (name "unconnected-(U1A-PC10-Pad51)") (class "Default")
      (node (ref "U1") (pin "51") (pinfunction "PC10_51") (pintype "bidirectional"))
    )
    (net (code "78") (name "unconnected-(U1A-PC11-Pad52)") (class "Default")
      (node (ref "U1") (pin "52") (pinfunction "PC11_52") (pintype "bidirectional"))
    )
    (net (code "79") (name "unconnected-(U1A-PC12-Pad53)") (class "Default")
      (node (ref "U1") (pin "53") (pinfunction "PC12_53") (pintype "bidirectional"))
    )
    (net (code "80") (name "unconnected-(U1A-PC13-TAMPER-RTC-Pad2)") (class "Default")
      (node (ref "U1") (pin "2") (pinfunction "PC13-TAMPER-RTC_2") (pintype "bidirectional"))
    )
    (net (code "81") (name "unconnected-(U1A-PD2-Pad54)") (class "Default")
      (node (ref "U1") (pin "54") (pinfunction "PD2_54") (pintype "bidirectional"))
    )
    (net (code "82") (name "unconnected-(U2-WP-Pad7)") (class "Default")
      (node (ref "U2") (pin "7") (pinfunction "WP_7") (pintype "input"))
    )
    (net (code "83") (name "unconnected-(U5-SHDN-Pad5)") (class "Default")
      (node (ref "U5") (pin "5") (pinfunction "SHDN_5") (pintype "passive"))
    )
  )
)
